# uTCA_Tongue3.net
KiCad netlist of a schematic drawn in Altium Designer
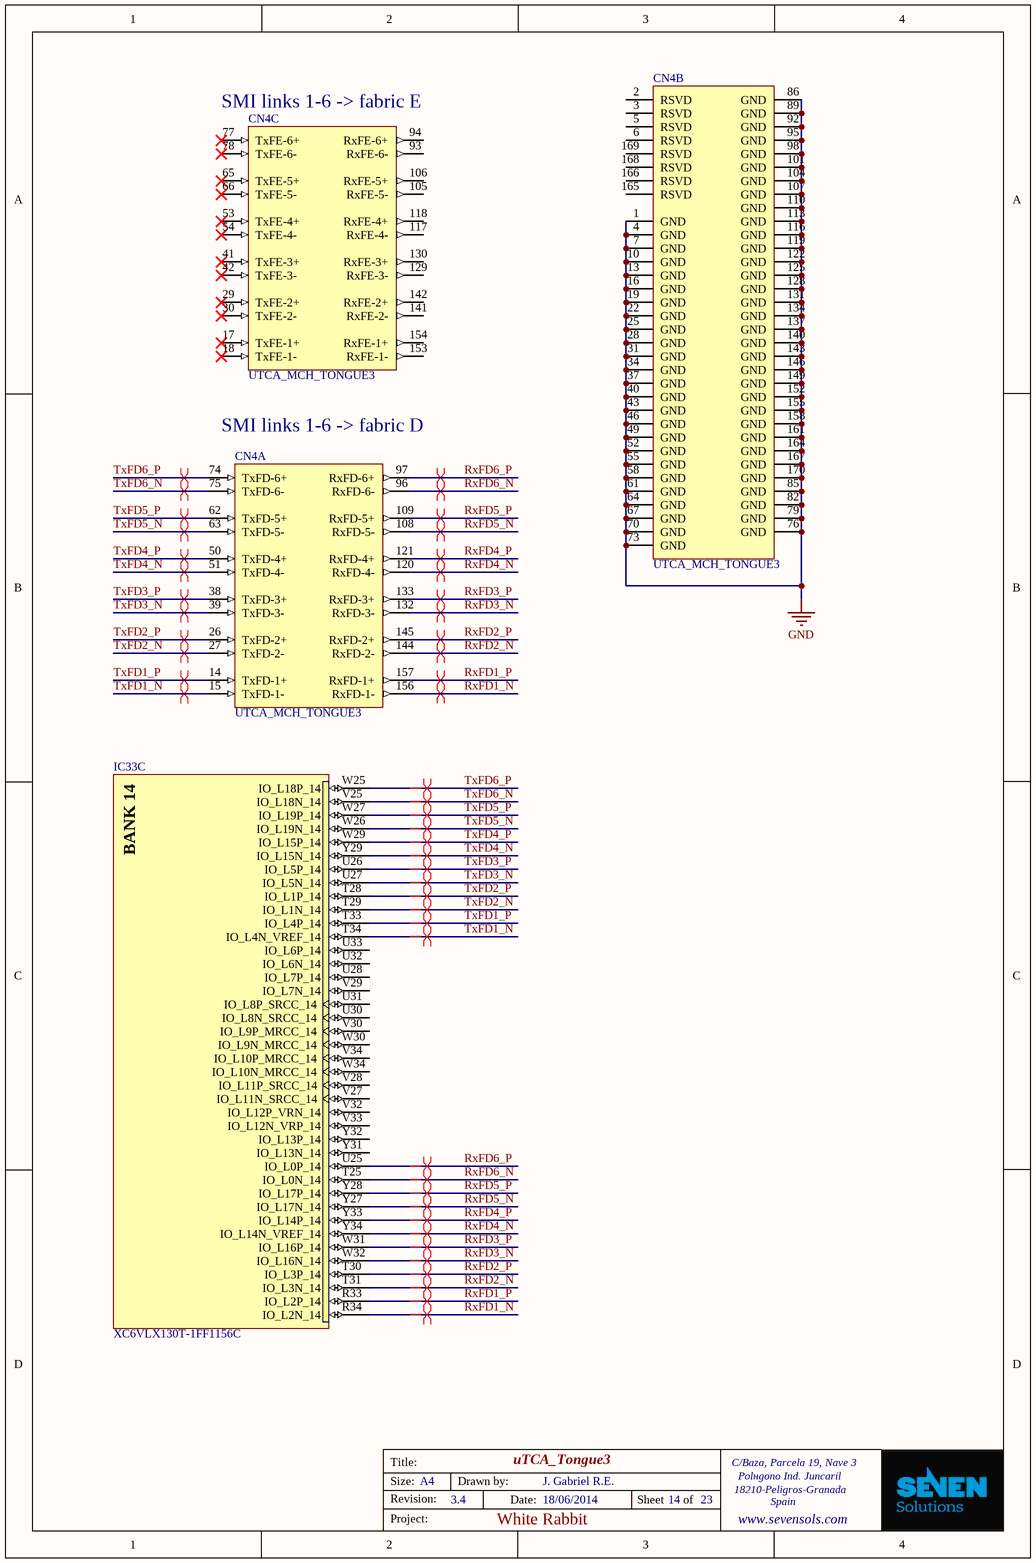
[diagram p0: uTCA_Tongue3.SchDoc]

(export (version "E")
  (design (tool "Eeschema 10.0.6"))
  (components
    (comp (ref "CN4")
      (value "UTCA_MCH_TONGUE3")
      (footprint "UTCA_MCH_TONGUE2_3_4")
      (description "microTCA MTCA.0 standard MCH connector 3")
      (libsource (lib "wr_switch") (part "UTCA_MCH_TONGUE3"))
    )
    (comp (ref "IC33")
      (value "XC6VLX130T-1FF1156C")
      (footprint "FF1156")
      (fields (field (name "PUBLISHER") "Altium Limited"))
      (libsource (lib "Xilinx Virtex-6") (part "XC6VLX130T-1FF1156C"))
    )
  )
  (nets
    (net (code "1") (name "/RxFD1_N") (class "Default")
      (node (ref "CN4") (pin "156") (pinfunction "RxFD-1-_156") (pintype "output"))
      (node (ref "IC33") (pin "R34") (pinfunction "IO_L2N_14_R34") (pintype "bidirectional"))
    )
    (net (code "2") (name "/RxFD1_P") (class "Default")
      (node (ref "CN4") (pin "157") (pinfunction "RxFD-1+_157") (pintype "output"))
      (node (ref "IC33") (pin "R33") (pinfunction "IO_L2P_14_R33") (pintype "bidirectional"))
    )
    (net (code "3") (name "/RxFD2_N") (class "Default")
      (node (ref "CN4") (pin "144") (pinfunction "RxFD-2-_144") (pintype "output"))
      (node (ref "IC33") (pin "T31") (pinfunction "IO_L3N_14_T31") (pintype "bidirectional"))
    )
    (net (code "4") (name "/RxFD2_P") (class "Default")
      (node (ref "CN4") (pin "145") (pinfunction "RxFD-2+_145") (pintype "output"))
      (node (ref "IC33") (pin "T30") (pinfunction "IO_L3P_14_T30") (pintype "bidirectional"))
    )
    (net (code "5") (name "/RxFD3_N") (class "Default")
      (node (ref "CN4") (pin "132") (pinfunction "RxFD-3-_132") (pintype "output"))
      (node (ref "IC33") (pin "W32") (pinfunction "IO_L16N_14_W32") (pintype "bidirectional"))
    )
    (net (code "6") (name "/RxFD3_P") (class "Default")
      (node (ref "CN4") (pin "133") (pinfunction "RxFD-3+_133") (pintype "output"))
      (node (ref "IC33") (pin "W31") (pinfunction "IO_L16P_14_W31") (pintype "bidirectional"))
    )
    (net (code "7") (name "/RxFD4_N") (class "Default")
      (node (ref "CN4") (pin "120") (pinfunction "RxFD-4-_120") (pintype "output"))
      (node (ref "IC33") (pin "Y34") (pinfunction "IO_L14N_VREF_14_Y34") (pintype "bidirectional"))
    )
    (net (code "8") (name "/RxFD4_P") (class "Default")
      (node (ref "CN4") (pin "121") (pinfunction "RxFD-4+_121") (pintype "output"))
      (node (ref "IC33") (pin "Y33") (pinfunction "IO_L14P_14_Y33") (pintype "bidirectional"))
    )
    (net (code "9") (name "/RxFD5_N") (class "Default")
      (node (ref "CN4") (pin "108") (pinfunction "RxFD-5-_108") (pintype "output"))
      (node (ref "IC33") (pin "Y27") (pinfunction "IO_L17N_14_Y27") (pintype "bidirectional"))
    )
    (net (code "10") (name "/RxFD5_P") (class "Default")
      (node (ref "CN4") (pin "109") (pinfunction "RxFD-5+_109") (pintype "output"))
      (node (ref "IC33") (pin "Y28") (pinfunction "IO_L17P_14_Y28") (pintype "bidirectional"))
    )
    (net (code "11") (name "/RxFD6_N") (class "Default")
      (node (ref "CN4") (pin "96") (pinfunction "RxFD-6-_96") (pintype "output"))
      (node (ref "IC33") (pin "T25") (pinfunction "IO_L0N_14_T25") (pintype "bidirectional"))
    )
    (net (code "12") (name "/RxFD6_P") (class "Default")
      (node (ref "CN4") (pin "97") (pinfunction "RxFD-6+_97") (pintype "output"))
      (node (ref "IC33") (pin "U25") (pinfunction "IO_L0P_14_U25") (pintype "bidirectional"))
    )
    (net (code "13") (name "/TxFD1_N") (class "Default")
      (node (ref "CN4") (pin "15") (pinfunction "TxFD-1-_15") (pintype "input"))
      (node (ref "IC33") (pin "T34") (pinfunction "IO_L4N_VREF_14_T34") (pintype "bidirectional"))
    )
    (net (code "14") (name "/TxFD1_P") (class "Default")
      (node (ref "CN4") (pin "14") (pinfunction "TxFD-1+_14") (pintype "input"))
      (node (ref "IC33") (pin "T33") (pinfunction "IO_L4P_14_T33") (pintype "bidirectional"))
    )
    (net (code "15") (name "/TxFD2_N") (class "Default")
      (node (ref "CN4") (pin "27") (pinfunction "TxFD-2-_27") (pintype "input"))
      (node (ref "IC33") (pin "T29") (pinfunction "IO_L1N_14_T29") (pintype "bidirectional"))
    )
    (net (code "16") (name "/TxFD2_P") (class "Default")
      (node (ref "CN4") (pin "26") (pinfunction "TxFD-2+_26") (pintype "input"))
      (node (ref "IC33") (pin "T28") (pinfunction "IO_L1P_14_T28") (pintype "bidirectional"))
    )
    (net (code "17") (name "/TxFD3_N") (class "Default")
      (node (ref "CN4") (pin "39") (pinfunction "TxFD-3-_39") (pintype "input"))
      (node (ref "IC33") (pin "U27") (pinfunction "IO_L5N_14_U27") (pintype "bidirectional"))
    )
    (net (code "18") (name "/TxFD3_P") (class "Default")
      (node (ref "CN4") (pin "38") (pinfunction "TxFD-3+_38") (pintype "input"))
      (node (ref "IC33") (pin "U26") (pinfunction "IO_L5P_14_U26") (pintype "bidirectional"))
    )
    (net (code "19") (name "/TxFD4_N") (class "Default")
      (node (ref "CN4") (pin "51") (pinfunction "TxFD-4-_51") (pintype "input"))
      (node (ref "IC33") (pin "Y29") (pinfunction "IO_L15N_14_Y29") (pintype "bidirectional"))
    )
    (net (code "20") (name "/TxFD4_P") (class "Default")
      (node (ref "CN4") (pin "50") (pinfunction "TxFD-4+_50") (pintype "input"))
      (node (ref "IC33") (pin "W29") (pinfunction "IO_L15P_14_W29") (pintype "bidirectional"))
    )
    (net (code "21") (name "/TxFD5_N") (class "Default")
      (node (ref "CN4") (pin "63") (pinfunction "TxFD-5-_63") (pintype "input"))
      (node (ref "IC33") (pin "W26") (pinfunction "IO_L19N_14_W26") (pintype "bidirectional"))
    )
    (net (code "22") (name "/TxFD5_P") (class "Default")
      (node (ref "CN4") (pin "62") (pinfunction "TxFD-5+_62") (pintype "input"))
      (node (ref "IC33") (pin "W27") (pinfunction "IO_L19P_14_W27") (pintype "bidirectional"))
    )
    (net (code "23") (name "/TxFD6_N") (class "Default")
      (node (ref "CN4") (pin "75") (pinfunction "TxFD-6-_75") (pintype "input"))
      (node (ref "IC33") (pin "V25") (pinfunction "IO_L18N_14_V25") (pintype "bidirectional"))
    )
    (net (code "24") (name "/TxFD6_P") (class "Default")
      (node (ref "CN4") (pin "74") (pinfunction "TxFD-6+_74") (pintype "input"))
      (node (ref "IC33") (pin "W25") (pinfunction "IO_L18P_14_W25") (pintype "bidirectional"))
    )
    (net (code "25") (name "GND") (class "Default")
      (node (ref "CN4") (pin "1") (pinfunction "GND_1") (pintype "power_in"))
      (node (ref "CN4") (pin "10") (pinfunction "GND_10") (pintype "power_in"))
      (node (ref "CN4") (pin "101") (pinfunction "GND_101") (pintype "power_in"))
      (node (ref "CN4") (pin "104") (pinfunction "GND_104") (pintype "power_in"))
      (node (ref "CN4") (pin "107") (pinfunction "GND_107") (pintype "power_in"))
      (node (ref "CN4") (pin "110") (pinfunction "GND_110") (pintype "power_in"))
      (node (ref "CN4") (pin "113") (pinfunction "GND_113") (pintype "power_in"))
      (node (ref "CN4") (pin "116") (pinfunction "GND_116") (pintype "power_in"))
      (node (ref "CN4") (pin "119") (pinfunction "GND_119") (pintype "power_in"))
      (node (ref "CN4") (pin "122") (pinfunction "GND_122") (pintype "power_in"))
      (node (ref "CN4") (pin "125") (pinfunction "GND_125") (pintype "power_in"))
      (node (ref "CN4") (pin "128") (pinfunction "GND_128") (pintype "power_in"))
      (node (ref "CN4") (pin "13") (pinfunction "GND_13") (pintype "power_in"))
      (node (ref "CN4") (pin "131") (pinfunction "GND_131") (pintype "power_in"))
      (node (ref "CN4") (pin "134") (pinfunction "GND_134") (pintype "power_in"))
      (node (ref "CN4") (pin "137") (pinfunction "GND_137") (pintype "power_in"))
      (node (ref "CN4") (pin "140") (pinfunction "GND_140") (pintype "power_in"))
      (node (ref "CN4") (pin "143") (pinfunction "GND_143") (pintype "power_in"))
      (node (ref "CN4") (pin "146") (pinfunction "GND_146") (pintype "power_in"))
      (node (ref "CN4") (pin "149") (pinfunction "GND_149") (pintype "power_in"))
      (node (ref "CN4") (pin "152") (pinfunction "GND_152") (pintype "power_in"))
      (node (ref "CN4") (pin "155") (pinfunction "GND_155") (pintype "power_in"))
      (node (ref "CN4") (pin "158") (pinfunction "GND_158") (pintype "power_in"))
      (node (ref "CN4") (pin "16") (pinfunction "GND_16") (pintype "power_in"))
      (node (ref "CN4") (pin "161") (pinfunction "GND_161") (pintype "power_in"))
      (node (ref "CN4") (pin "164") (pinfunction "GND_164") (pintype "power_in"))
      (node (ref "CN4") (pin "167") (pinfunction "GND_167") (pintype "power_in"))
      (node (ref "CN4") (pin "170") (pinfunction "GND_170") (pintype "power_in"))
      (node (ref "CN4") (pin "19") (pinfunction "GND_19") (pintype "power_in"))
      (node (ref "CN4") (pin "22") (pinfunction "GND_22") (pintype "power_in"))
      (node (ref "CN4") (pin "25") (pinfunction "GND_25") (pintype "power_in"))
      (node (ref "CN4") (pin "28") (pinfunction "GND_28") (pintype "power_in"))
      (node (ref "CN4") (pin "31") (pinfunction "GND_31") (pintype "power_in"))
      (node (ref "CN4") (pin "34") (pinfunction "GND_34") (pintype "power_in"))
      (node (ref "CN4") (pin "37") (pinfunction "GND_37") (pintype "power_in"))
      (node (ref "CN4") (pin "4") (pinfunction "GND_4") (pintype "power_in"))
      (node (ref "CN4") (pin "40") (pinfunction "GND_40") (pintype "power_in"))
      (node (ref "CN4") (pin "43") (pinfunction "GND_43") (pintype "power_in"))
      (node (ref "CN4") (pin "46") (pinfunction "GND_46") (pintype "power_in"))
      (node (ref "CN4") (pin "49") (pinfunction "GND_49") (pintype "power_in"))
      (node (ref "CN4") (pin "52") (pinfunction "GND_52") (pintype "power_in"))
      (node (ref "CN4") (pin "55") (pinfunction "GND_55") (pintype "power_in"))
      (node (ref "CN4") (pin "58") (pinfunction "GND_58") (pintype "power_in"))
      (node (ref "CN4") (pin "61") (pinfunction "GND_61") (pintype "power_in"))
      (node (ref "CN4") (pin "64") (pinfunction "GND_64") (pintype "power_in"))
      (node (ref "CN4") (pin "67") (pinfunction "GND_67") (pintype "power_in"))
      (node (ref "CN4") (pin "7") (pinfunction "GND_7") (pintype "power_in"))
      (node (ref "CN4") (pin "70") (pinfunction "GND_70") (pintype "power_in"))
      (node (ref "CN4") (pin "73") (pinfunction "GND_73") (pintype "power_in"))
      (node (ref "CN4") (pin "76") (pinfunction "GND_76") (pintype "power_in"))
      (node (ref "CN4") (pin "79") (pinfunction "GND_79") (pintype "power_in"))
      (node (ref "CN4") (pin "82") (pinfunction "GND_82") (pintype "power_in"))
      (node (ref "CN4") (pin "85") (pinfunction "GND_85") (pintype "power_in"))
      (node (ref "CN4") (pin "86") (pinfunction "GND_86") (pintype "power_in"))
      (node (ref "CN4") (pin "89") (pinfunction "GND_89") (pintype "power_in"))
      (node (ref "CN4") (pin "92") (pinfunction "GND_92") (pintype "power_in"))
      (node (ref "CN4") (pin "95") (pinfunction "GND_95") (pintype "power_in"))
      (node (ref "CN4") (pin "98") (pinfunction "GND_98") (pintype "power_in"))
    )
    (net (code "26") (name "unconnected-(CN4B-RSVD-Pad2)") (class "Default")
      (node (ref "CN4") (pin "2") (pinfunction "RSVD_2") (pintype "passive"))
    )
    (net (code "27") (name "unconnected-(CN4B-RSVD-Pad3)") (class "Default")
      (node (ref "CN4") (pin "3") (pinfunction "RSVD_3") (pintype "passive"))
    )
    (net (code "28") (name "unconnected-(CN4B-RSVD-Pad5)") (class "Default")
      (node (ref "CN4") (pin "5") (pinfunction "RSVD_5") (pintype "passive"))
    )
    (net (code "29") (name "unconnected-(CN4B-RSVD-Pad6)") (class "Default")
      (node (ref "CN4") (pin "6") (pinfunction "RSVD_6") (pintype "passive"))
    )
    (net (code "30") (name "unconnected-(CN4B-RSVD-Pad165)") (class "Default")
      (node (ref "CN4") (pin "165") (pinfunction "RSVD_165") (pintype "passive"))
    )
    (net (code "31") (name "unconnected-(CN4B-RSVD-Pad166)") (class "Default")
      (node (ref "CN4") (pin "166") (pinfunction "RSVD_166") (pintype "passive"))
    )
    (net (code "32") (name "unconnected-(CN4B-RSVD-Pad168)") (class "Default")
      (node (ref "CN4") (pin "168") (pinfunction "RSVD_168") (pintype "passive"))
    )
    (net (code "33") (name "unconnected-(CN4B-RSVD-Pad169)") (class "Default")
      (node (ref "CN4") (pin "169") (pinfunction "RSVD_169") (pintype "passive"))
    )
    (net (code "34") (name "unconnected-(CN4C-RxFE-1+-Pad154)") (class "Default")
      (node (ref "CN4") (pin "154") (pinfunction "RxFE-1+_154") (pintype "output"))
    )
    (net (code "35") (name "unconnected-(CN4C-RxFE-1--Pad153)") (class "Default")
      (node (ref "CN4") (pin "153") (pinfunction "RxFE-1-_153") (pintype "output"))
    )
    (net (code "36") (name "unconnected-(CN4C-RxFE-2+-Pad142)") (class "Default")
      (node (ref "CN4") (pin "142") (pinfunction "RxFE-2+_142") (pintype "output"))
    )
    (net (code "37") (name "unconnected-(CN4C-RxFE-2--Pad141)") (class "Default")
      (node (ref "CN4") (pin "141") (pinfunction "RxFE-2-_141") (pintype "output"))
    )
    (net (code "38") (name "unconnected-(CN4C-RxFE-3+-Pad130)") (class "Default")
      (node (ref "CN4") (pin "130") (pinfunction "RxFE-3+_130") (pintype "output"))
    )
    (net (code "39") (name "unconnected-(CN4C-RxFE-3--Pad129)") (class "Default")
      (node (ref "CN4") (pin "129") (pinfunction "RxFE-3-_129") (pintype "output"))
    )
    (net (code "40") (name "unconnected-(CN4C-RxFE-4+-Pad118)") (class "Default")
      (node (ref "CN4") (pin "118") (pinfunction "RxFE-4+_118") (pintype "output"))
    )
    (net (code "41") (name "unconnected-(CN4C-RxFE-4--Pad117)") (class "Default")
      (node (ref "CN4") (pin "117") (pinfunction "RxFE-4-_117") (pintype "output"))
    )
    (net (code "42") (name "unconnected-(CN4C-RxFE-5+-Pad106)") (class "Default")
      (node (ref "CN4") (pin "106") (pinfunction "RxFE-5+_106") (pintype "output"))
    )
    (net (code "43") (name "unconnected-(CN4C-RxFE-5--Pad105)") (class "Default")
      (node (ref "CN4") (pin "105") (pinfunction "RxFE-5-_105") (pintype "output"))
    )
    (net (code "44") (name "unconnected-(CN4C-RxFE-6+-Pad94)") (class "Default")
      (node (ref "CN4") (pin "94") (pinfunction "RxFE-6+_94") (pintype "output"))
    )
    (net (code "45") (name "unconnected-(CN4C-RxFE-6--Pad93)") (class "Default")
      (node (ref "CN4") (pin "93") (pinfunction "RxFE-6-_93") (pintype "output"))
    )
    (net (code "46") (name "unconnected-(CN4C-TxFE-1+-Pad17)") (class "Default")
      (node (ref "CN4") (pin "17") (pinfunction "TxFE-1+_17") (pintype "input+no_connect"))
    )
    (net (code "47") (name "unconnected-(CN4C-TxFE-1--Pad18)") (class "Default")
      (node (ref "CN4") (pin "18") (pinfunction "TxFE-1-_18") (pintype "input+no_connect"))
    )
    (net (code "48") (name "unconnected-(CN4C-TxFE-2+-Pad29)") (class "Default")
      (node (ref "CN4") (pin "29") (pinfunction "TxFE-2+_29") (pintype "input+no_connect"))
    )
    (net (code "49") (name "unconnected-(CN4C-TxFE-2--Pad30)") (class "Default")
      (node (ref "CN4") (pin "30") (pinfunction "TxFE-2-_30") (pintype "input+no_connect"))
    )
    (net (code "50") (name "unconnected-(CN4C-TxFE-3+-Pad41)") (class "Default")
      (node (ref "CN4") (pin "41") (pinfunction "TxFE-3+_41") (pintype "input+no_connect"))
    )
    (net (code "51") (name "unconnected-(CN4C-TxFE-3--Pad42)") (class "Default")
      (node (ref "CN4") (pin "42") (pinfunction "TxFE-3-_42") (pintype "input+no_connect"))
    )
    (net (code "52") (name "unconnected-(CN4C-TxFE-4+-Pad53)") (class "Default")
      (node (ref "CN4") (pin "53") (pinfunction "TxFE-4+_53") (pintype "input+no_connect"))
    )
    (net (code "53") (name "unconnected-(CN4C-TxFE-4--Pad54)") (class "Default")
      (node (ref "CN4") (pin "54") (pinfunction "TxFE-4-_54") (pintype "input+no_connect"))
    )
    (net (code "54") (name "unconnected-(CN4C-TxFE-5+-Pad65)") (class "Default")
      (node (ref "CN4") (pin "65") (pinfunction "TxFE-5+_65") (pintype "input+no_connect"))
    )
    (net (code "55") (name "unconnected-(CN4C-TxFE-5--Pad66)") (class "Default")
      (node (ref "CN4") (pin "66") (pinfunction "TxFE-5-_66") (pintype "input+no_connect"))
    )
    (net (code "56") (name "unconnected-(CN4C-TxFE-6+-Pad77)") (class "Default")
      (node (ref "CN4") (pin "77") (pinfunction "TxFE-6+_77") (pintype "input+no_connect"))
    )
    (net (code "57") (name "unconnected-(CN4C-TxFE-6--Pad78)") (class "Default")
      (node (ref "CN4") (pin "78") (pinfunction "TxFE-6-_78") (pintype "input+no_connect"))
    )
    (net (code "58") (name "unconnected-(IC33C-IO_L6N_14-PadU32)") (class "Default")
      (node (ref "IC33") (pin "U32") (pinfunction "IO_L6N_14_U32") (pintype "bidirectional"))
    )
    (net (code "59") (name "unconnected-(IC33C-IO_L6P_14-PadU33)") (class "Default")
      (node (ref "IC33") (pin "U33") (pinfunction "IO_L6P_14_U33") (pintype "bidirectional"))
    )
    (net (code "60") (name "unconnected-(IC33C-IO_L7N_14-PadV29)") (class "Default")
      (node (ref "IC33") (pin "V29") (pinfunction "IO_L7N_14_V29") (pintype "bidirectional"))
    )
    (net (code "61") (name "unconnected-(IC33C-IO_L7P_14-PadU28)") (class "Default")
      (node (ref "IC33") (pin "U28") (pinfunction "IO_L7P_14_U28") (pintype "bidirectional"))
    )
    (net (code "62") (name "unconnected-(IC33C-IO_L8N_SRCC_14-PadU30)") (class "Default")
      (node (ref "IC33") (pin "U30") (pinfunction "IO_L8N_SRCC_14_U30") (pintype "bidirectional"))
    )
    (net (code "63") (name "unconnected-(IC33C-IO_L8P_SRCC_14-PadU31)") (class "Default")
      (node (ref "IC33") (pin "U31") (pinfunction "IO_L8P_SRCC_14_U31") (pintype "bidirectional"))
    )
    (net (code "64") (name "unconnected-(IC33C-IO_L9N_MRCC_14-PadW30)") (class "Default")
      (node (ref "IC33") (pin "W30") (pinfunction "IO_L9N_MRCC_14_W30") (pintype "bidirectional"))
    )
    (net (code "65") (name "unconnected-(IC33C-IO_L9P_MRCC_14-PadV30)") (class "Default")
      (node (ref "IC33") (pin "V30") (pinfunction "IO_L9P_MRCC_14_V30") (pintype "bidirectional"))
    )
    (net (code "66") (name "unconnected-(IC33C-IO_L10N_MRCC_14-PadW34)") (class "Default")
      (node (ref "IC33") (pin "W34") (pinfunction "IO_L10N_MRCC_14_W34") (pintype "bidirectional"))
    )
    (net (code "67") (name "unconnected-(IC33C-IO_L10P_MRCC_14-PadV34)") (class "Default")
      (node (ref "IC33") (pin "V34") (pinfunction "IO_L10P_MRCC_14_V34") (pintype "bidirectional"))
    )
    (net (code "68") (name "unconnected-(IC33C-IO_L11N_SRCC_14-PadV27)") (class "Default")
      (node (ref "IC33") (pin "V27") (pinfunction "IO_L11N_SRCC_14_V27") (pintype "bidirectional"))
    )
    (net (code "69") (name "unconnected-(IC33C-IO_L11P_SRCC_14-PadV28)") (class "Default")
      (node (ref "IC33") (pin "V28") (pinfunction "IO_L11P_SRCC_14_V28") (pintype "bidirectional"))
    )
    (net (code "70") (name "unconnected-(IC33C-IO_L12N_VRP_14-PadV33)") (class "Default")
      (node (ref "IC33") (pin "V33") (pinfunction "IO_L12N_VRP_14_V33") (pintype "bidirectional"))
    )
    (net (code "71") (name "unconnected-(IC33C-IO_L12P_VRN_14-PadV32)") (class "Default")
      (node (ref "IC33") (pin "V32") (pinfunction "IO_L12P_VRN_14_V32") (pintype "bidirectional"))
    )
    (net (code "72") (name "unconnected-(IC33C-IO_L13N_14-PadY31)") (class "Default")
      (node (ref "IC33") (pin "Y31") (pinfunction "IO_L13N_14_Y31") (pintype "bidirectional"))
    )
    (net (code "73") (name "unconnected-(IC33C-IO_L13P_14-PadY32)") (class "Default")
      (node (ref "IC33") (pin "Y32") (pinfunction "IO_L13P_14_Y32") (pintype "bidirectional"))
    )
  )
)
